# 5V_Regulator.net
KiCad netlist of a schematic drawn in Altium Designer
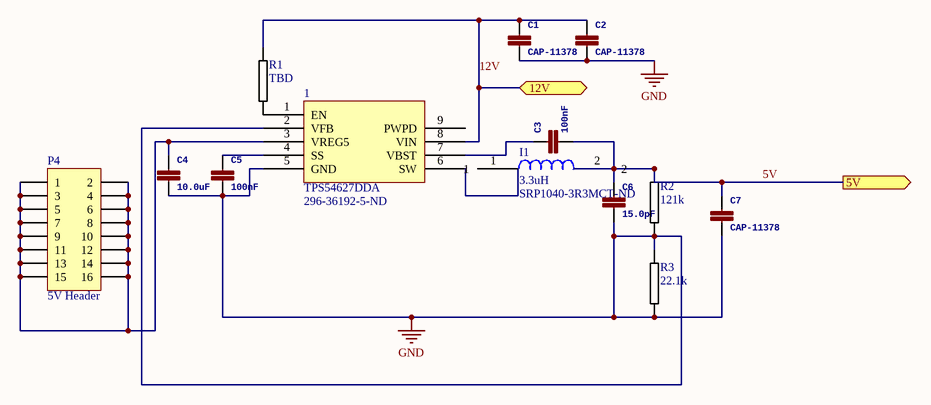
[diagram p0: 5V Regulator.SchDoc]

(export (version "E")
  (design (tool "Eeschema 10.0.6"))
  (components
    (comp (ref "1")
      (value "TPS54627DDA")
      (footprint "SOIC127P600X170_HS-9N")
      (description "IC REG BUCK ADJ 6A SYNC 8SOPWR")
      (fields
        (field (name "MANUFACTURER") "Texas Instruments")
        (field (name "BASE PART NUMBER") "TPS54627")
        (field (name "SUPPLIER PART NUMBER 1") "296-36192-5-ND")
      )
      (libsource (lib "Digi_Key") (part "TPS54627DDA"))
    )
    (comp (ref "C1")
      (value "CAP-11378")
      (footprint "0603")
      (libsource (lib "SparkFun-Retired") (part "4.7NF-50V-10%(0603)"))
    )
    (comp (ref "C2")
      (value "CAP-11378")
      (footprint "0603")
      (libsource (lib "SparkFun-Retired") (part "4.7NF-50V-10%(0603)"))
    )
    (comp (ref "C3") (value "100nF") (footprint "0603") (libsource (lib "") (part "4.7NF-50V-10%(0603)_1")))
    (comp (ref "C4")
      (value "10.0uF")
      (footprint "0603")
      (libsource (lib "SparkFun-Retired") (part "4.7NF-50V-10%(0603)"))
    )
    (comp (ref "C5")
      (value "100nF")
      (footprint "0603")
      (libsource (lib "SparkFun-Retired") (part "4.7NF-50V-10%(0603)"))
    )
    (comp (ref "C6")
      (value "15.0pF")
      (footprint "0603")
      (libsource (lib "SparkFun-Retired") (part "4.7NF-50V-10%(0603)"))
    )
    (comp (ref "C7")
      (value "CAP-11378")
      (footprint "0603")
      (libsource (lib "SparkFun-Retired") (part "4.7NF-50V-10%(0603)"))
    )
    (comp (ref "I1")
      (value "3.3uH")
      (footprint "SRP1040")
      (description "FIXED IND 3.3UH 10A 10 MOHM SMD")
      (fields
        (field (name "MANUFACTURER") "Bourns Inc.")
        (field (name "MANUFACTURER PART NUMBER") "SRP1040-3R3M")
        (field (name "SUPPLIER PART NUMBER 1") "SRP1040-3R3MCT-ND")
      )
      (libsource (lib "Digi_Key") (part "SRP1040-3R3M"))
    )
    (comp (ref "P4")
      (value "5V Header")
      (footprint "HDR2X8H")
      (description "Header, 8-Pin, Dual row, Right Angle")
      (fields (field (name "PUBLISHER") "Altium Limited"))
      (libsource (lib "Miscellaneous Connectors") (part "Header 8X2H"))
    )
    (comp (ref "R1")
      (value "TBD")
      (footprint "0402R-TBD")
      (description "RESISTOR 0402 VALUE TO BE DETERMINED")
      (libsource (lib "vh_altium_library") (part "0402R-TBD"))
    )
    (comp (ref "R2")
      (value "121k")
      (footprint "0402R-TBD")
      (description "RESISTOR 0402 VALUE TO BE DETERMINED")
      (libsource (lib "vh_altium_library") (part "0402R-TBD"))
    )
    (comp (ref "R3")
      (value "22.1k")
      (footprint "0402R-TBD")
      (description "RESISTOR 0402 VALUE TO BE DETERMINED")
      (libsource (lib "vh_altium_library") (part "0402R-TBD"))
    )
  )
  (nets
    (net (code "1") (name "/5V") (class "Default")
      (node (ref "C3") (pin "2") (pinfunction "2_2") (pintype "passive"))
      (node (ref "C6") (pin "1") (pinfunction "1_1") (pintype "passive"))
      (node (ref "C7") (pin "1") (pinfunction "1_1") (pintype "passive"))
      (node (ref "I1") (pin "2") (pinfunction "2_2") (pintype "passive"))
      (node (ref "R2") (pin "1") (pintype "passive"))
    )
    (net (code "2") (name "/12V") (class "Default")
      (node (ref "1") (pin "8") (pinfunction "VIN_8") (pintype "passive"))
      (node (ref "C1") (pin "1") (pinfunction "1_1") (pintype "passive"))
      (node (ref "C2") (pin "1") (pinfunction "1_1") (pintype "passive"))
      (node (ref "R1") (pin "1") (pintype "passive"))
    )
    (net (code "3") (name "GND") (class "Default")
      (node (ref "1") (pin "2") (pinfunction "VFB_2") (pintype "passive"))
      (node (ref "1") (pin "5") (pinfunction "GND_5") (pintype "passive"))
      (node (ref "C1") (pin "2") (pinfunction "2_2") (pintype "passive"))
      (node (ref "C2") (pin "2") (pinfunction "2_2") (pintype "passive"))
      (node (ref "C4") (pin "2") (pinfunction "2_2") (pintype "passive"))
      (node (ref "C5") (pin "2") (pinfunction "2_2") (pintype "passive"))
      (node (ref "C6") (pin "2") (pinfunction "2_2") (pintype "passive"))
      (node (ref "C7") (pin "2") (pinfunction "2_2") (pintype "passive"))
      (node (ref "R2") (pin "2") (pintype "passive"))
      (node (ref "R3") (pin "1") (pintype "passive"))
      (node (ref "R3") (pin "2") (pintype "passive"))
    )
    (net (code "4") (name "Net-(1-EN)") (class "Default")
      (node (ref "1") (pin "1") (pinfunction "EN_1") (pintype "passive"))
      (node (ref "R1") (pin "2") (pintype "passive"))
    )
    (net (code "5") (name "Net-(1-SS)") (class "Default")
      (node (ref "1") (pin "4") (pinfunction "SS_4") (pintype "passive"))
      (node (ref "C5") (pin "1") (pinfunction "1_1") (pintype "passive"))
    )
    (net (code "6") (name "Net-(1-SW)") (class "Default")
      (node (ref "1") (pin "6") (pinfunction "SW_6") (pintype "passive"))
      (node (ref "I1") (pin "1") (pinfunction "1_1") (pintype "passive"))
    )
    (net (code "7") (name "Net-(1-VBST)") (class "Default")
      (node (ref "1") (pin "7") (pinfunction "VBST_7") (pintype "passive"))
      (node (ref "C3") (pin "1") (pinfunction "1_1") (pintype "passive"))
    )
    (net (code "8") (name "Net-(1-VREG5)") (class "Default")
      (node (ref "1") (pin "3") (pinfunction "VREG5_3") (pintype "passive"))
      (node (ref "C4") (pin "1") (pinfunction "1_1") (pintype "passive"))
      (node (ref "P4") (pin "1") (pinfunction "1_1") (pintype "passive"))
      (node (ref "P4") (pin "10") (pinfunction "10_10") (pintype "passive"))
      (node (ref "P4") (pin "11") (pinfunction "11_11") (pintype "passive"))
      (node (ref "P4") (pin "12") (pinfunction "12_12") (pintype "passive"))
      (node (ref "P4") (pin "13") (pinfunction "13_13") (pintype "passive"))
      (node (ref "P4") (pin "14") (pinfunction "14_14") (pintype "passive"))
      (node (ref "P4") (pin "15") (pinfunction "15_15") (pintype "passive"))
      (node (ref "P4") (pin "16") (pinfunction "16_16") (pintype "passive"))
      (node (ref "P4") (pin "2") (pinfunction "2_2") (pintype "passive"))
      (node (ref "P4") (pin "3") (pinfunction "3_3") (pintype "passive"))
      (node (ref "P4") (pin "4") (pinfunction "4_4") (pintype "passive"))
      (node (ref "P4") (pin "5") (pinfunction "5_5") (pintype "passive"))
      (node (ref "P4") (pin "6") (pinfunction "6_6") (pintype "passive"))
      (node (ref "P4") (pin "7") (pinfunction "7_7") (pintype "passive"))
      (node (ref "P4") (pin "8") (pinfunction "8_8") (pintype "passive"))
      (node (ref "P4") (pin "9") (pinfunction "9_9") (pintype "passive"))
    )
    (net (code "9") (name "unconnected-(1-PWPD-Pad9)") (class "Default")
      (node (ref "1") (pin "9") (pinfunction "PWPD_9") (pintype "passive"))
    )
  )
)
